# design.net
KiCad netlist of a schematic drawn in Altium Designer
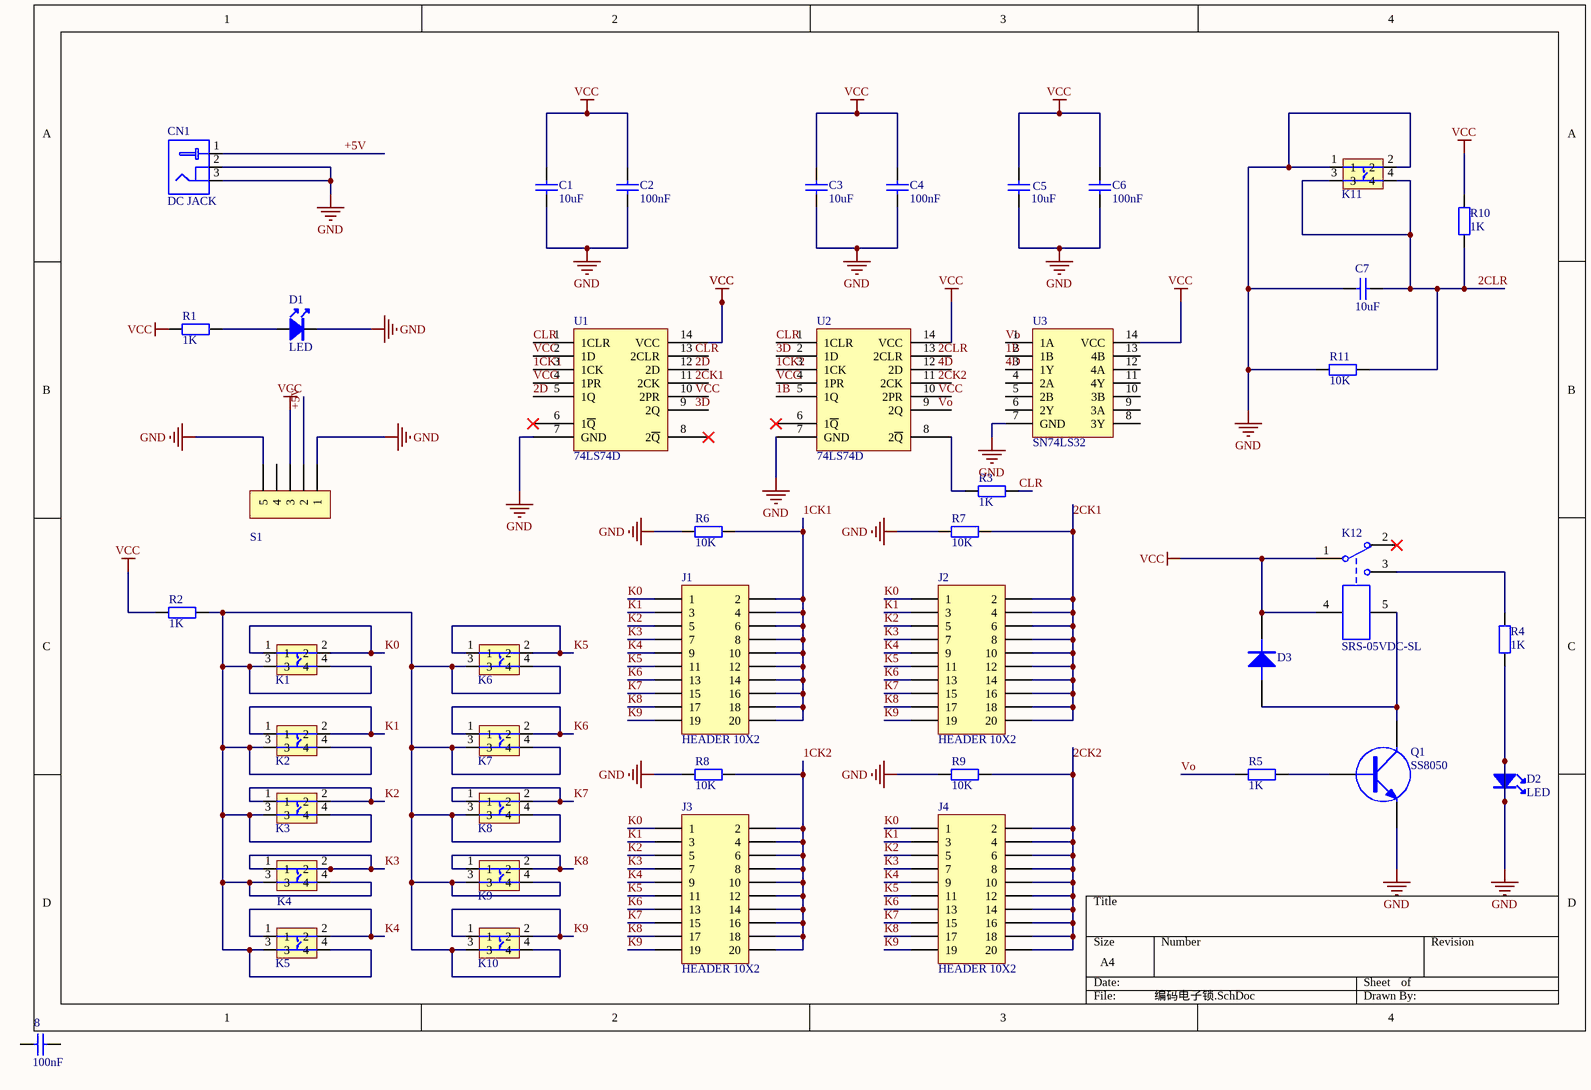
[diagram p0: 编码电子锁.SchDoc]

(export (version "E")
  (design (tool "Eeschema 10.0.6"))
  (components
    (comp (ref "8")
      (value "100nF")
      (footprint "0805")
      (description "100nF，0805，+/-10%")
      (fields (field (name "PUBLISHER") "Altium Limited"))
      (libsource (lib "编码电子锁") (part "电容"))
    )
    (comp (ref "C1")
      (value "10uF")
      (footprint "0805")
      (description "10uF，0805，25V,+/-10%")
      (fields (field (name "PUBLISHER") "Altium Limited"))
      (libsource (lib "四人抢答器") (part "Cap"))
    )
    (comp (ref "C2")
      (value "100nF")
      (footprint "0805")
      (description "100nF，0805，+/-10%")
      (fields (field (name "PUBLISHER") "Altium Limited"))
      (libsource (lib "编码电子锁") (part "电容"))
    )
    (comp (ref "C3")
      (value "10uF")
      (footprint "0805")
      (description "10uF，0805，25V,+/-10%")
      (fields (field (name "PUBLISHER") "Altium Limited"))
      (libsource (lib "四人抢答器") (part "Cap"))
    )
    (comp (ref "C4")
      (value "100nF")
      (footprint "0805")
      (description "100nF，0805，+/-10%")
      (fields (field (name "PUBLISHER") "Altium Limited"))
      (libsource (lib "编码电子锁") (part "电容"))
    )
    (comp (ref "C5")
      (value "10uF")
      (footprint "0805")
      (description "10uF，0805，25V,+/-10%")
      (fields (field (name "PUBLISHER") "Altium Limited"))
      (libsource (lib "四人抢答器") (part "Cap"))
    )
    (comp (ref "C6")
      (value "100nF")
      (footprint "0805")
      (description "100nF，0805，+/-10%")
      (fields (field (name "PUBLISHER") "Altium Limited"))
      (libsource (lib "编码电子锁") (part "电容"))
    )
    (comp (ref "C7")
      (value "10uF")
      (footprint "0805")
      (description "10uF，0805，25V,+/-10%")
      (fields (field (name "PUBLISHER") "Altium Limited"))
      (libsource (lib "编码电子锁") (part "Cap"))
    )
    (comp (ref "CN1")
      (value "DC JACK")
      (footprint "DC JACK")
      (description "DC JACK电源插座,5.5mm孔径,3脚接插件")
      (libsource (lib "我的元件库") (part "DC JACK"))
    )
    (comp (ref "D1")
      (value "LED")
      (footprint "3MM插件LED")
      (description "3MM插件LED，绿发绿光，3mm")
      (libsource (lib "我的元件库") (part "3MM插件LED"))
    )
    (comp (ref "D2")
      (value "LED")
      (footprint "3MM插件LED")
      (description "3MM插件LED，绿发绿光，3mm")
      (libsource (lib "编码电子锁") (part "3MM插件LED"))
    )
    (comp (ref "D3") (value "1N4148") (footprint "1N5819") (libsource (lib "编码电子锁") (part "DIODE_1")))
    (comp (ref "J1")
      (value "HEADER 10X2")
      (footprint "HDR2X10")
      (libsource (lib "编码电子锁") (part "HEADER 10X2"))
    )
    (comp (ref "J2")
      (value "HEADER 10X2")
      (footprint "HDR2X10")
      (libsource (lib "编码电子锁") (part "HEADER 10X2"))
    )
    (comp (ref "J3")
      (value "HEADER 10X2")
      (footprint "HDR2X10")
      (libsource (lib "编码电子锁") (part "HEADER 10X2"))
    )
    (comp (ref "J4")
      (value "HEADER 10X2")
      (footprint "HDR2X10")
      (libsource (lib "编码电子锁") (part "HEADER 10X2"))
    )
    (comp (ref "K1")
      (value "SW6X6轻触开关")
      (footprint "SW6X6轻触开关")
      (description "6*6mm*4.5mm轻触开关,4脚插件,180°")
      (libsource (lib "编码电子锁") (part "SW6X6轻触开关"))
    )
    (comp (ref "K2")
      (value "SW6X6轻触开关")
      (footprint "SW6X6轻触开关")
      (description "6*6mm*4.5mm轻触开关,4脚插件,180°")
      (libsource (lib "编码电子锁") (part "SW6X6轻触开关"))
    )
    (comp (ref "K3")
      (value "SW6X6轻触开关")
      (footprint "SW6X6轻触开关")
      (description "6*6mm*4.5mm轻触开关,4脚插件,180°")
      (libsource (lib "编码电子锁") (part "SW6X6轻触开关"))
    )
    (comp (ref "K4")
      (value "SW6X6轻触开关")
      (footprint "SW6X6轻触开关")
      (description "6*6mm*4.5mm轻触开关,4脚插件,180°")
      (libsource (lib "编码电子锁") (part "SW6X6轻触开关"))
    )
    (comp (ref "K5")
      (value "SW6X6轻触开关")
      (footprint "SW6X6轻触开关")
      (description "6*6mm*4.5mm轻触开关,4脚插件,180°")
      (libsource (lib "编码电子锁") (part "SW6X6轻触开关"))
    )
    (comp (ref "K6")
      (value "SW6X6轻触开关")
      (footprint "SW6X6轻触开关")
      (description "6*6mm*4.5mm轻触开关,4脚插件,180°")
      (libsource (lib "编码电子锁") (part "SW6X6轻触开关"))
    )
    (comp (ref "K7")
      (value "SW6X6轻触开关")
      (footprint "SW6X6轻触开关")
      (description "6*6mm*4.5mm轻触开关,4脚插件,180°")
      (libsource (lib "编码电子锁") (part "SW6X6轻触开关"))
    )
    (comp (ref "K8")
      (value "SW6X6轻触开关")
      (footprint "SW6X6轻触开关")
      (description "6*6mm*4.5mm轻触开关,4脚插件,180°")
      (libsource (lib "编码电子锁") (part "SW6X6轻触开关"))
    )
    (comp (ref "K9")
      (value "SW6X6轻触开关")
      (footprint "SW6X6轻触开关")
      (description "6*6mm*4.5mm轻触开关,4脚插件,180°")
      (libsource (lib "编码电子锁") (part "SW6X6轻触开关"))
    )
    (comp (ref "K10")
      (value "SW6X6轻触开关")
      (footprint "SW6X6轻触开关")
      (description "6*6mm*4.5mm轻触开关,4脚插件,180°")
      (libsource (lib "编码电子锁") (part "SW6X6轻触开关"))
    )
    (comp (ref "K11")
      (value "SW6X6轻触开关")
      (footprint "SW6X6轻触开关")
      (description "6*6mm*4.5mm轻触开关,4脚插件,180°")
      (libsource (lib "编码电子锁") (part "SW6X6轻触开关"))
    )
    (comp (ref "K12") (value "SRS-05VDC-SL") (footprint "继电器") (libsource (lib "编码电子锁") (part "继电器")))
    (comp (ref "Q1")
      (value "SS8050")
      (footprint "S8050")
      (description "SOT23,3-pin,NPN型三极管，s8050")
      (libsource (lib "编码电子锁") (part "S8050"))
    )
    (comp (ref "R1")
      (value "1K")
      (footprint "0805")
      (description "10kΩ，0805，+/-5%")
      (fields (field (name "PUBLISHER") "Altium Limited"))
      (libsource (lib "四人抢答器") (part "电阻"))
    )
    (comp (ref "R2")
      (value "1K")
      (footprint "0805")
      (description "10kΩ，0805，+/-5%")
      (fields (field (name "PUBLISHER") "Altium Limited"))
      (libsource (lib "") (part "电阻_1"))
    )
    (comp (ref "R3")
      (value "1K")
      (footprint "0805")
      (description "10kΩ，0805，+/-5%")
      (fields (field (name "PUBLISHER") "Altium Limited"))
      (libsource (lib "四人抢答器") (part "电阻"))
    )
    (comp (ref "R4")
      (value "1K")
      (footprint "0805")
      (description "10kΩ，0805，+/-5%")
      (fields (field (name "PUBLISHER") "Altium Limited"))
      (libsource (lib "编码电子锁") (part "电阻"))
    )
    (comp (ref "R5")
      (value "1K")
      (footprint "0805")
      (description "10kΩ，0805，+/-5%")
      (fields (field (name "PUBLISHER") "Altium Limited"))
      (libsource (lib "") (part "电阻_1"))
    )
    (comp (ref "R6")
      (value "10K")
      (footprint "0805")
      (description "10kΩ，0805，+/-5%")
      (fields (field (name "PUBLISHER") "Altium Limited"))
      (libsource (lib "四人抢答器") (part "电阻"))
    )
    (comp (ref "R7")
      (value "10K")
      (footprint "0805")
      (description "10kΩ，0805，+/-5%")
      (fields (field (name "PUBLISHER") "Altium Limited"))
      (libsource (lib "四人抢答器") (part "电阻"))
    )
    (comp (ref "R8")
      (value "10K")
      (footprint "0805")
      (description "10kΩ，0805，+/-5%")
      (fields (field (name "PUBLISHER") "Altium Limited"))
      (libsource (lib "四人抢答器") (part "电阻"))
    )
    (comp (ref "R9")
      (value "10K")
      (footprint "0805")
      (description "10kΩ，0805，+/-5%")
      (fields (field (name "PUBLISHER") "Altium Limited"))
      (libsource (lib "四人抢答器") (part "电阻"))
    )
    (comp (ref "R10")
      (value "1K")
      (footprint "0805")
      (description "10kΩ，0805，+/-5%")
      (fields (field (name "PUBLISHER") "Altium Limited"))
      (libsource (lib "编码电子锁") (part "电阻"))
    )
    (comp (ref "R11")
      (value "10K")
      (footprint "0805")
      (description "10kΩ，0805，+/-5%")
      (fields (field (name "PUBLISHER") "Altium Limited"))
      (libsource (lib "") (part "电阻_1"))
    )
    (comp (ref "S1")
      (value "CON5")
      (footprint "拨动开关5脚")
      (description "SWITCH")
      (libsource (lib "我的元件库") (part "拨动开关5脚"))
    )
    (comp (ref "U1") (value "74LS74D") (footprint "74LS74D") (libsource (lib "我的元件库") (part "74LS74D")))
    (comp (ref "U2") (value "74LS74D") (footprint "74LS74D") (libsource (lib "我的元件库") (part "74LS74D")))
    (comp (ref "U3") (value "SN74LS32") (footprint "74LS32") (libsource (lib "编码电子锁") (part "SN74LS32")))
  )
  (nets
    (net (code "1") (name "/+5V") (class "Default")
      (node (ref "CN1") (pin "1") (pintype "passive"))
      (node (ref "S1") (pin "2") (pinfunction "2_2") (pintype "passive"))
    )
    (net (code "2") (name "/1B") (class "Default")
      (node (ref "U2") (pin "5") (pinfunction "1Q_5") (pintype "passive"))
      (node (ref "U3") (pin "2") (pinfunction "1B_2") (pintype "passive"))
    )
    (net (code "3") (name "/1CK1") (class "Default")
      (node (ref "J1") (pin "10") (pinfunction "10_10") (pintype "passive"))
      (node (ref "J1") (pin "12") (pinfunction "12_12") (pintype "passive"))
      (node (ref "J1") (pin "14") (pinfunction "14_14") (pintype "passive"))
      (node (ref "J1") (pin "16") (pinfunction "16_16") (pintype "passive"))
      (node (ref "J1") (pin "18") (pinfunction "18_18") (pintype "passive"))
      (node (ref "J1") (pin "2") (pinfunction "2_2") (pintype "passive"))
      (node (ref "J1") (pin "20") (pinfunction "20_20") (pintype "passive"))
      (node (ref "J1") (pin "4") (pinfunction "4_4") (pintype "passive"))
      (node (ref "J1") (pin "6") (pinfunction "6_6") (pintype "passive"))
      (node (ref "J1") (pin "8") (pinfunction "8_8") (pintype "passive"))
      (node (ref "R6") (pin "2") (pinfunction "2_2") (pintype "passive"))
      (node (ref "U1") (pin "3") (pinfunction "1CK_3") (pintype "passive"))
    )
    (net (code "4") (name "/1CK2") (class "Default")
      (node (ref "J3") (pin "10") (pinfunction "10_10") (pintype "passive"))
      (node (ref "J3") (pin "12") (pinfunction "12_12") (pintype "passive"))
      (node (ref "J3") (pin "14") (pinfunction "14_14") (pintype "passive"))
      (node (ref "J3") (pin "16") (pinfunction "16_16") (pintype "passive"))
      (node (ref "J3") (pin "18") (pinfunction "18_18") (pintype "passive"))
      (node (ref "J3") (pin "2") (pinfunction "2_2") (pintype "passive"))
      (node (ref "J3") (pin "20") (pinfunction "20_20") (pintype "passive"))
      (node (ref "J3") (pin "4") (pinfunction "4_4") (pintype "passive"))
      (node (ref "J3") (pin "6") (pinfunction "6_6") (pintype "passive"))
      (node (ref "J3") (pin "8") (pinfunction "8_8") (pintype "passive"))
      (node (ref "R8") (pin "2") (pinfunction "2_2") (pintype "passive"))
      (node (ref "U2") (pin "3") (pinfunction "1CK_3") (pintype "passive"))
    )
    (net (code "5") (name "/2CK1") (class "Default")
      (node (ref "J2") (pin "10") (pinfunction "10_10") (pintype "passive"))
      (node (ref "J2") (pin "12") (pinfunction "12_12") (pintype "passive"))
      (node (ref "J2") (pin "14") (pinfunction "14_14") (pintype "passive"))
      (node (ref "J2") (pin "16") (pinfunction "16_16") (pintype "passive"))
      (node (ref "J2") (pin "18") (pinfunction "18_18") (pintype "passive"))
      (node (ref "J2") (pin "2") (pinfunction "2_2") (pintype "passive"))
      (node (ref "J2") (pin "20") (pinfunction "20_20") (pintype "passive"))
      (node (ref "J2") (pin "4") (pinfunction "4_4") (pintype "passive"))
      (node (ref "J2") (pin "6") (pinfunction "6_6") (pintype "passive"))
      (node (ref "J2") (pin "8") (pinfunction "8_8") (pintype "passive"))
      (node (ref "R7") (pin "2") (pinfunction "2_2") (pintype "passive"))
    )
    (net (code "6") (name "/2CK2") (class "Default")
      (node (ref "J4") (pin "10") (pinfunction "10_10") (pintype "passive"))
      (node (ref "J4") (pin "12") (pinfunction "12_12") (pintype "passive"))
      (node (ref "J4") (pin "14") (pinfunction "14_14") (pintype "passive"))
      (node (ref "J4") (pin "16") (pinfunction "16_16") (pintype "passive"))
      (node (ref "J4") (pin "18") (pinfunction "18_18") (pintype "passive"))
      (node (ref "J4") (pin "2") (pinfunction "2_2") (pintype "passive"))
      (node (ref "J4") (pin "20") (pinfunction "20_20") (pintype "passive"))
      (node (ref "J4") (pin "4") (pinfunction "4_4") (pintype "passive"))
      (node (ref "J4") (pin "6") (pinfunction "6_6") (pintype "passive"))
      (node (ref "J4") (pin "8") (pinfunction "8_8") (pintype "passive"))
      (node (ref "R9") (pin "2") (pinfunction "2_2") (pintype "passive"))
    )
    (net (code "7") (name "/2CLR") (class "Default")
      (node (ref "C7") (pin "2") (pinfunction "2_2") (pintype "passive"))
      (node (ref "K11") (pin "3") (pinfunction "3_3") (pintype "passive"))
      (node (ref "K11") (pin "4") (pinfunction "4_4") (pintype "passive"))
      (node (ref "R10") (pin "1") (pinfunction "1_1") (pintype "passive"))
      (node (ref "R11") (pin "2") (pinfunction "2_2") (pintype "passive"))
    )
    (net (code "8") (name "/2D") (class "Default")
      (node (ref "U1") (pin "5") (pinfunction "1Q_5") (pintype "passive"))
    )
    (net (code "9") (name "/3D") (class "Default")
      (node (ref "U2") (pin "2") (pinfunction "1D_2") (pintype "passive"))
    )
    (net (code "10") (name "/4D") (class "Default")
      (node (ref "U3") (pin "3") (pinfunction "1Y_3") (pintype "passive"))
    )
    (net (code "12") (name "/CLR") (class "Default")
      (node (ref "R3") (pin "2") (pinfunction "2_2") (pintype "passive"))
      (node (ref "U1") (pin "1") (pinfunction "1CLR_1") (pintype "passive"))
      (node (ref "U2") (pin "1") (pinfunction "1CLR_1") (pintype "passive"))
    )
    (net (code "13") (name "/K0") (class "Default")
      (node (ref "J1") (pin "1") (pinfunction "1_1") (pintype "passive"))
      (node (ref "J2") (pin "1") (pinfunction "1_1") (pintype "passive"))
      (node (ref "J3") (pin "1") (pinfunction "1_1") (pintype "passive"))
      (node (ref "J4") (pin "1") (pinfunction "1_1") (pintype "passive"))
      (node (ref "K1") (pin "1") (pinfunction "1_1") (pintype "passive"))
      (node (ref "K1") (pin "2") (pinfunction "2_2") (pintype "passive"))
    )
    (net (code "14") (name "/K1") (class "Default")
      (node (ref "J1") (pin "3") (pinfunction "3_3") (pintype "passive"))
      (node (ref "J2") (pin "3") (pinfunction "3_3") (pintype "passive"))
      (node (ref "J3") (pin "3") (pinfunction "3_3") (pintype "passive"))
      (node (ref "J4") (pin "3") (pinfunction "3_3") (pintype "passive"))
      (node (ref "K2") (pin "1") (pinfunction "1_1") (pintype "passive"))
      (node (ref "K2") (pin "2") (pinfunction "2_2") (pintype "passive"))
    )
    (net (code "15") (name "/K2") (class "Default")
      (node (ref "J1") (pin "5") (pinfunction "5_5") (pintype "passive"))
      (node (ref "J2") (pin "5") (pinfunction "5_5") (pintype "passive"))
      (node (ref "J3") (pin "5") (pinfunction "5_5") (pintype "passive"))
      (node (ref "J4") (pin "5") (pinfunction "5_5") (pintype "passive"))
      (node (ref "K3") (pin "1") (pinfunction "1_1") (pintype "passive"))
      (node (ref "K3") (pin "2") (pinfunction "2_2") (pintype "passive"))
    )
    (net (code "16") (name "/K3") (class "Default")
      (node (ref "J1") (pin "7") (pinfunction "7_7") (pintype "passive"))
      (node (ref "J2") (pin "7") (pinfunction "7_7") (pintype "passive"))
      (node (ref "J3") (pin "7") (pinfunction "7_7") (pintype "passive"))
      (node (ref "J4") (pin "7") (pinfunction "7_7") (pintype "passive"))
      (node (ref "K4") (pin "1") (pinfunction "1_1") (pintype "passive"))
      (node (ref "K4") (pin "2") (pinfunction "2_2") (pintype "passive"))
    )
    (net (code "17") (name "/K4") (class "Default")
      (node (ref "J1") (pin "9") (pinfunction "9_9") (pintype "passive"))
      (node (ref "J2") (pin "9") (pinfunction "9_9") (pintype "passive"))
      (node (ref "J3") (pin "9") (pinfunction "9_9") (pintype "passive"))
      (node (ref "J4") (pin "9") (pinfunction "9_9") (pintype "passive"))
      (node (ref "K5") (pin "1") (pinfunction "1_1") (pintype "passive"))
      (node (ref "K5") (pin "2") (pinfunction "2_2") (pintype "passive"))
    )
    (net (code "18") (name "/K5") (class "Default")
      (node (ref "J1") (pin "11") (pinfunction "11_11") (pintype "passive"))
      (node (ref "J2") (pin "11") (pinfunction "11_11") (pintype "passive"))
      (node (ref "J3") (pin "11") (pinfunction "11_11") (pintype "passive"))
      (node (ref "J4") (pin "11") (pinfunction "11_11") (pintype "passive"))
      (node (ref "K6") (pin "1") (pinfunction "1_1") (pintype "passive"))
      (node (ref "K6") (pin "2") (pinfunction "2_2") (pintype "passive"))
    )
    (net (code "19") (name "/K6") (class "Default")
      (node (ref "J1") (pin "13") (pinfunction "13_13") (pintype "passive"))
      (node (ref "J2") (pin "13") (pinfunction "13_13") (pintype "passive"))
      (node (ref "J3") (pin "13") (pinfunction "13_13") (pintype "passive"))
      (node (ref "J4") (pin "13") (pinfunction "13_13") (pintype "passive"))
      (node (ref "K7") (pin "1") (pinfunction "1_1") (pintype "passive"))
      (node (ref "K7") (pin "2") (pinfunction "2_2") (pintype "passive"))
    )
    (net (code "20") (name "/K7") (class "Default")
      (node (ref "J1") (pin "15") (pinfunction "15_15") (pintype "passive"))
      (node (ref "J2") (pin "15") (pinfunction "15_15") (pintype "passive"))
      (node (ref "J3") (pin "15") (pinfunction "15_15") (pintype "passive"))
      (node (ref "J4") (pin "15") (pinfunction "15_15") (pintype "passive"))
      (node (ref "K8") (pin "1") (pinfunction "1_1") (pintype "passive"))
      (node (ref "K8") (pin "2") (pinfunction "2_2") (pintype "passive"))
    )
    (net (code "21") (name "/K8") (class "Default")
      (node (ref "J1") (pin "17") (pinfunction "17_17") (pintype "passive"))
      (node (ref "J2") (pin "17") (pinfunction "17_17") (pintype "passive"))
      (node (ref "J3") (pin "17") (pinfunction "17_17") (pintype "passive"))
      (node (ref "J4") (pin "17") (pinfunction "17_17") (pintype "passive"))
      (node (ref "K9") (pin "1") (pinfunction "1_1") (pintype "passive"))
      (node (ref "K9") (pin "2") (pinfunction "2_2") (pintype "passive"))
    )
    (net (code "22") (name "/K9") (class "Default")
      (node (ref "J1") (pin "19") (pinfunction "19_19") (pintype "passive"))
      (node (ref "J2") (pin "19") (pinfunction "19_19") (pintype "passive"))
      (node (ref "J3") (pin "19") (pinfunction "19_19") (pintype "passive"))
      (node (ref "J4") (pin "19") (pinfunction "19_19") (pintype "passive"))
      (node (ref "K10") (pin "1") (pinfunction "1_1") (pintype "passive"))
      (node (ref "K10") (pin "2") (pinfunction "2_2") (pintype "passive"))
    )
    (net (code "23") (name "/Vo") (class "Default")
      (node (ref "R5") (pin "1") (pinfunction "1_1") (pintype "passive"))
      (node (ref "U3") (pin "1") (pinfunction "1A_1") (pintype "passive"))
    )
    (net (code "24") (name "GND") (class "Default")
      (node (ref "C1") (pin "1") (pinfunction "1_1") (pintype "passive"))
      (node (ref "C2") (pin "1") (pinfunction "1_1") (pintype "passive"))
      (node (ref "C3") (pin "1") (pinfunction "1_1") (pintype "passive"))
      (node (ref "C4") (pin "1") (pinfunction "1_1") (pintype "passive"))
      (node (ref "C5") (pin "1") (pinfunction "1_1") (pintype "passive"))
      (node (ref "C6") (pin "2") (pinfunction "2_2") (pintype "passive"))
      (node (ref "C7") (pin "1") (pinfunction "1_1") (pintype "passive"))
      (node (ref "CN1") (pin "2") (pintype "passive"))
      (node (ref "CN1") (pin "3") (pintype "passive"))
      (node (ref "D1") (pin "2") (pinfunction "2_2") (pintype "passive"))
      (node (ref "D2") (pin "1") (pinfunction "1_1") (pintype "passive"))
      (node (ref "D2") (pin "2") (pinfunction "2_2") (pintype "passive"))
      (node (ref "K11") (pin "1") (pinfunction "1_1") (pintype "passive"))
      (node (ref "K11") (pin "2") (pinfunction "2_2") (pintype "passive"))
      (node (ref "Q1") (pin "2") (pinfunction "E_2") (pintype "passive"))
      (node (ref "R11") (pin "1") (pinfunction "1_1") (pintype "passive"))
      (node (ref "R4") (pin "1") (pinfunction "1_1") (pintype "passive"))
      (node (ref "R6") (pin "1") (pinfunction "1_1") (pintype "passive"))
      (node (ref "R7") (pin "1") (pinfunction "1_1") (pintype "passive"))
      (node (ref "R8") (pin "1") (pinfunction "1_1") (pintype "passive"))
      (node (ref "R9") (pin "1") (pinfunction "1_1") (pintype "passive"))
      (node (ref "S1") (pin "1") (pinfunction "1_1") (pintype "passive"))
      (node (ref "S1") (pin "5") (pinfunction "5_5") (pintype "passive"))
      (node (ref "U1") (pin "7") (pinfunction "GND_7") (pintype "passive"))
      (node (ref "U2") (pin "7") (pinfunction "GND_7") (pintype "passive"))
      (node (ref "U3") (pin "7") (pinfunction "GND_7") (pintype "passive"))
    )
    (net (code "25") (name "Net-(D1-Pad1)") (class "Default")
      (node (ref "D1") (pin "1") (pinfunction "1_1") (pintype "passive"))
      (node (ref "R1") (pin "2") (pinfunction "2_2") (pintype "passive"))
    )
    (net (code "26") (name "Net-(D3-A)") (class "Default")
      (node (ref "D3") (pin "1") (pinfunction "A_1") (pintype "passive"))
      (node (ref "K12") (pin "5") (pinfunction "5_5") (pintype "passive"))
      (node (ref "Q1") (pin "3") (pinfunction "C_3") (pintype "passive"))
    )
    (net (code "27") (name "Net-(K1-Pad3)") (class "Default")
      (node (ref "K1") (pin "3") (pinfunction "3_3") (pintype "passive"))
      (node (ref "K1") (pin "4") (pinfunction "4_4") (pintype "passive"))
      (node (ref "K10") (pin "3") (pinfunction "3_3") (pintype "passive"))
      (node (ref "K10") (pin "4") (pinfunction "4_4") (pintype "passive"))
      (node (ref "K2") (pin "3") (pinfunction "3_3") (pintype "passive"))
      (node (ref "K2") (pin "4") (pinfunction "4_4") (pintype "passive"))
      (node (ref "K3") (pin "3") (pinfunction "3_3") (pintype "passive"))
      (node (ref "K3") (pin "4") (pinfunction "4_4") (pintype "passive"))
      (node (ref "K4") (pin "3") (pinfunction "3_3") (pintype "passive"))
      (node (ref "K4") (pin "4") (pinfunction "4_4") (pintype "passive"))
      (node (ref "K5") (pin "3") (pinfunction "3_3") (pintype "passive"))
      (node (ref "K5") (pin "4") (pinfunction "4_4") (pintype "passive"))
      (node (ref "K6") (pin "3") (pinfunction "3_3") (pintype "passive"))
      (node (ref "K6") (pin "4") (pinfunction "4_4") (pintype "passive"))
      (node (ref "K7") (pin "3") (pinfunction "3_3") (pintype "passive"))
      (node (ref "K7") (pin "4") (pinfunction "4_4") (pintype "passive"))
      (node (ref "K8") (pin "3") (pinfunction "3_3") (pintype "passive"))
      (node (ref "K8") (pin "4") (pinfunction "4_4") (pintype "passive"))
      (node (ref "K9") (pin "3") (pinfunction "3_3") (pintype "passive"))
      (node (ref "K9") (pin "4") (pinfunction "4_4") (pintype "passive"))
      (node (ref "R2") (pin "2") (pinfunction "2_2") (pintype "passive"))
    )
    (net (code "28") (name "Net-(K12-Pad3)") (class "Default")
      (node (ref "K12") (pin "3") (pinfunction "3_3") (pintype "passive"))
      (node (ref "R4") (pin "2") (pinfunction "2_2") (pintype "passive"))
    )
    (net (code "29") (name "Net-(Q1-B)") (class "Default")
      (node (ref "Q1") (pin "1") (pinfunction "B_1") (pintype "passive"))
      (node (ref "R5") (pin "2") (pinfunction "2_2") (pintype "passive"))
    )
    (net (code "30") (name "Net-(U2-2~{Q})") (class "Default")
      (node (ref "R3") (pin "1") (pinfunction "1_1") (pintype "passive"))
      (node (ref "U2") (pin "8") (pinfunction "2~{Q}_8") (pintype "passive"))
    )
    (net (code "31") (name "VCC") (class "Default")
      (node (ref "C1") (pin "2") (pinfunction "2_2") (pintype "passive"))
      (node (ref "C2") (pin "2") (pinfunction "2_2") (pintype "passive"))
      (node (ref "C3") (pin "2") (pinfunction "2_2") (pintype "passive"))
      (node (ref "C4") (pin "2") (pinfunction "2_2") (pintype "passive"))
      (node (ref "C5") (pin "2") (pinfunction "2_2") (pintype "passive"))
      (node (ref "C6") (pin "1") (pinfunction "1_1") (pintype "passive"))
      (node (ref "D3") (pin "2") (pinfunction "K_2") (pintype "passive"))
      (node (ref "K12") (pin "1") (pinfunction "1_1") (pintype "passive"))
      (node (ref "K12") (pin "4") (pinfunction "4_4") (pintype "passive"))
      (node (ref "R1") (pin "1") (pinfunction "1_1") (pintype "passive"))
      (node (ref "R10") (pin "2") (pinfunction "2_2") (pintype "passive"))
      (node (ref "R2") (pin "1") (pinfunction "1_1") (pintype "passive"))
      (node (ref "S1") (pin "3") (pinfunction "3_3") (pintype "passive"))
      (node (ref "U1") (pin "14") (pinfunction "VCC_14") (pintype "passive"))
      (node (ref "U1") (pin "2") (pinfunction "1D_2") (pintype "passive"))
      (node (ref "U1") (pin "4") (pinfunction "1PR_4") (pintype "passive"))
      (node (ref "U2") (pin "14") (pinfunction "VCC_14") (pintype "passive"))
      (node (ref "U2") (pin "4") (pinfunction "1PR_4") (pintype "passive"))
      (node (ref "U3") (pin "14") (pinfunction "VCC_14") (pintype "passive"))
    )
    (net (code "32") (name "unconnected-(8-Pad1)") (class "Default")
      (node (ref "8") (pin "1") (pinfunction "1_1") (pintype "passive"))
    )
    (net (code "33") (name "unconnected-(8-Pad2)") (class "Default")
      (node (ref "8") (pin "2") (pinfunction "2_2") (pintype "passive"))
    )
    (net (code "34") (name "unconnected-(K12-Pad2)") (class "Default")
      (node (ref "K12") (pin "2") (pinfunction "2_2") (pintype "passive+no_connect"))
    )
    (net (code "35") (name "unconnected-(S1-Pad4)") (class "Default")
      (node (ref "S1") (pin "4") (pinfunction "4_4") (pintype "passive"))
    )
    (net (code "36") (name "unconnected-(U1-1~{Q}-Pad6)") (class "Default")
      (node (ref "U1") (pin "6") (pinfunction "1~{Q}_6") (pintype "passive+no_connect"))
    )
    (net (code "37") (name "unconnected-(U1-2CK-Pad11)") (class "Default")
      (node (ref "U1") (pin "11") (pinfunction "2CK_11") (pintype "passive"))
    )
    (net (code "38") (name "unconnected-(U1-2CLR-Pad13)") (class "Default")
      (node (ref "U1") (pin "13") (pinfunction "2CLR_13") (pintype "passive"))
    )
    (net (code "39") (name "unconnected-(U1-2D-Pad12)") (class "Default")
      (node (ref "U1") (pin "12") (pinfunction "2D_12") (pintype "passive"))
    )
    (net (code "40") (name "unconnected-(U1-2PR-Pad10)") (class "Default")
      (node (ref "U1") (pin "10") (pinfunction "2PR_10") (pintype "passive"))
    )
    (net (code "41") (name "unconnected-(U1-2Q-Pad9)") (class "Default")
      (node (ref "U1") (pin "9") (pinfunction "2Q_9") (pintype "passive"))
    )
    (net (code "42") (name "unconnected-(U1-2~{Q}-Pad8)") (class "Default")
      (node (ref "U1") (pin "8") (pinfunction "2~{Q}_8") (pintype "passive+no_connect"))
    )
    (net (code "43") (name "unconnected-(U2-1~{Q}-Pad6)") (class "Default")
      (node (ref "U2") (pin "6") (pinfunction "1~{Q}_6") (pintype "passive+no_connect"))
    )
    (net (code "44") (name "unconnected-(U2-2CK-Pad11)") (class "Default")
      (node (ref "U2") (pin "11") (pinfunction "2CK_11") (pintype "passive"))
    )
    (net (code "45") (name "unconnected-(U2-2CLR-Pad13)") (class "Default")
      (node (ref "U2") (pin "13") (pinfunction "2CLR_13") (pintype "passive"))
    )
    (net (code "46") (name "unconnected-(U2-2D-Pad12)") (class "Default")
      (node (ref "U2") (pin "12") (pinfunction "2D_12") (pintype "passive"))
    )
    (net (code "47") (name "unconnected-(U2-2PR-Pad10)") (class "Default")
      (node (ref "U2") (pin "10") (pinfunction "2PR_10") (pintype "passive"))
    )
    (net (code "48") (name "unconnected-(U2-2Q-Pad9)") (class "Default")
      (node (ref "U2") (pin "9") (pinfunction "2Q_9") (pintype "passive"))
    )
    (net (code "49") (name "unconnected-(U3-2A-Pad4)") (class "Default")
      (node (ref "U3") (pin "4") (pinfunction "2A_4") (pintype "passive"))
    )
    (net (code "50") (name "unconnected-(U3-2B-Pad5)") (class "Default")
      (node (ref "U3") (pin "5") (pinfunction "2B_5") (pintype "passive"))
    )
    (net (code "51") (name "unconnected-(U3-2Y-Pad6)") (class "Default")
      (node (ref "U3") (pin "6") (pinfunction "2Y_6") (pintype "passive"))
    )
    (net (code "52") (name "unconnected-(U3-3A-Pad9)") (class "Default")
      (node (ref "U3") (pin "9") (pinfunction "3A_9") (pintype "passive"))
    )
    (net (code "53") (name "unconnected-(U3-3B-Pad10)") (class "Default")
      (node (ref "U3") (pin "10") (pinfunction "3B_10") (pintype "passive"))
    )
    (net (code "54") (name "unconnected-(U3-3Y-Pad8)") (class "Default")
      (node (ref "U3") (pin "8") (pinfunction "3Y_8") (pintype "passive"))
    )
    (net (code "55") (name "unconnected-(U3-4A-Pad12)") (class "Default")
      (node (ref "U3") (pin "12") (pinfunction "4A_12") (pintype "passive"))
    )
    (net (code "56") (name "unconnected-(U3-4B-Pad13)") (class "Default")
      (node (ref "U3") (pin "13") (pinfunction "4B_13") (pintype "passive"))
    )
    (net (code "57") (name "unconnected-(U3-4Y-Pad11)") (class "Default")
      (node (ref "U3") (pin "11") (pinfunction "4Y_11") (pintype "passive"))
    )
  )
)
